# ALU.net
KiCad netlist of a schematic drawn in EAGLE
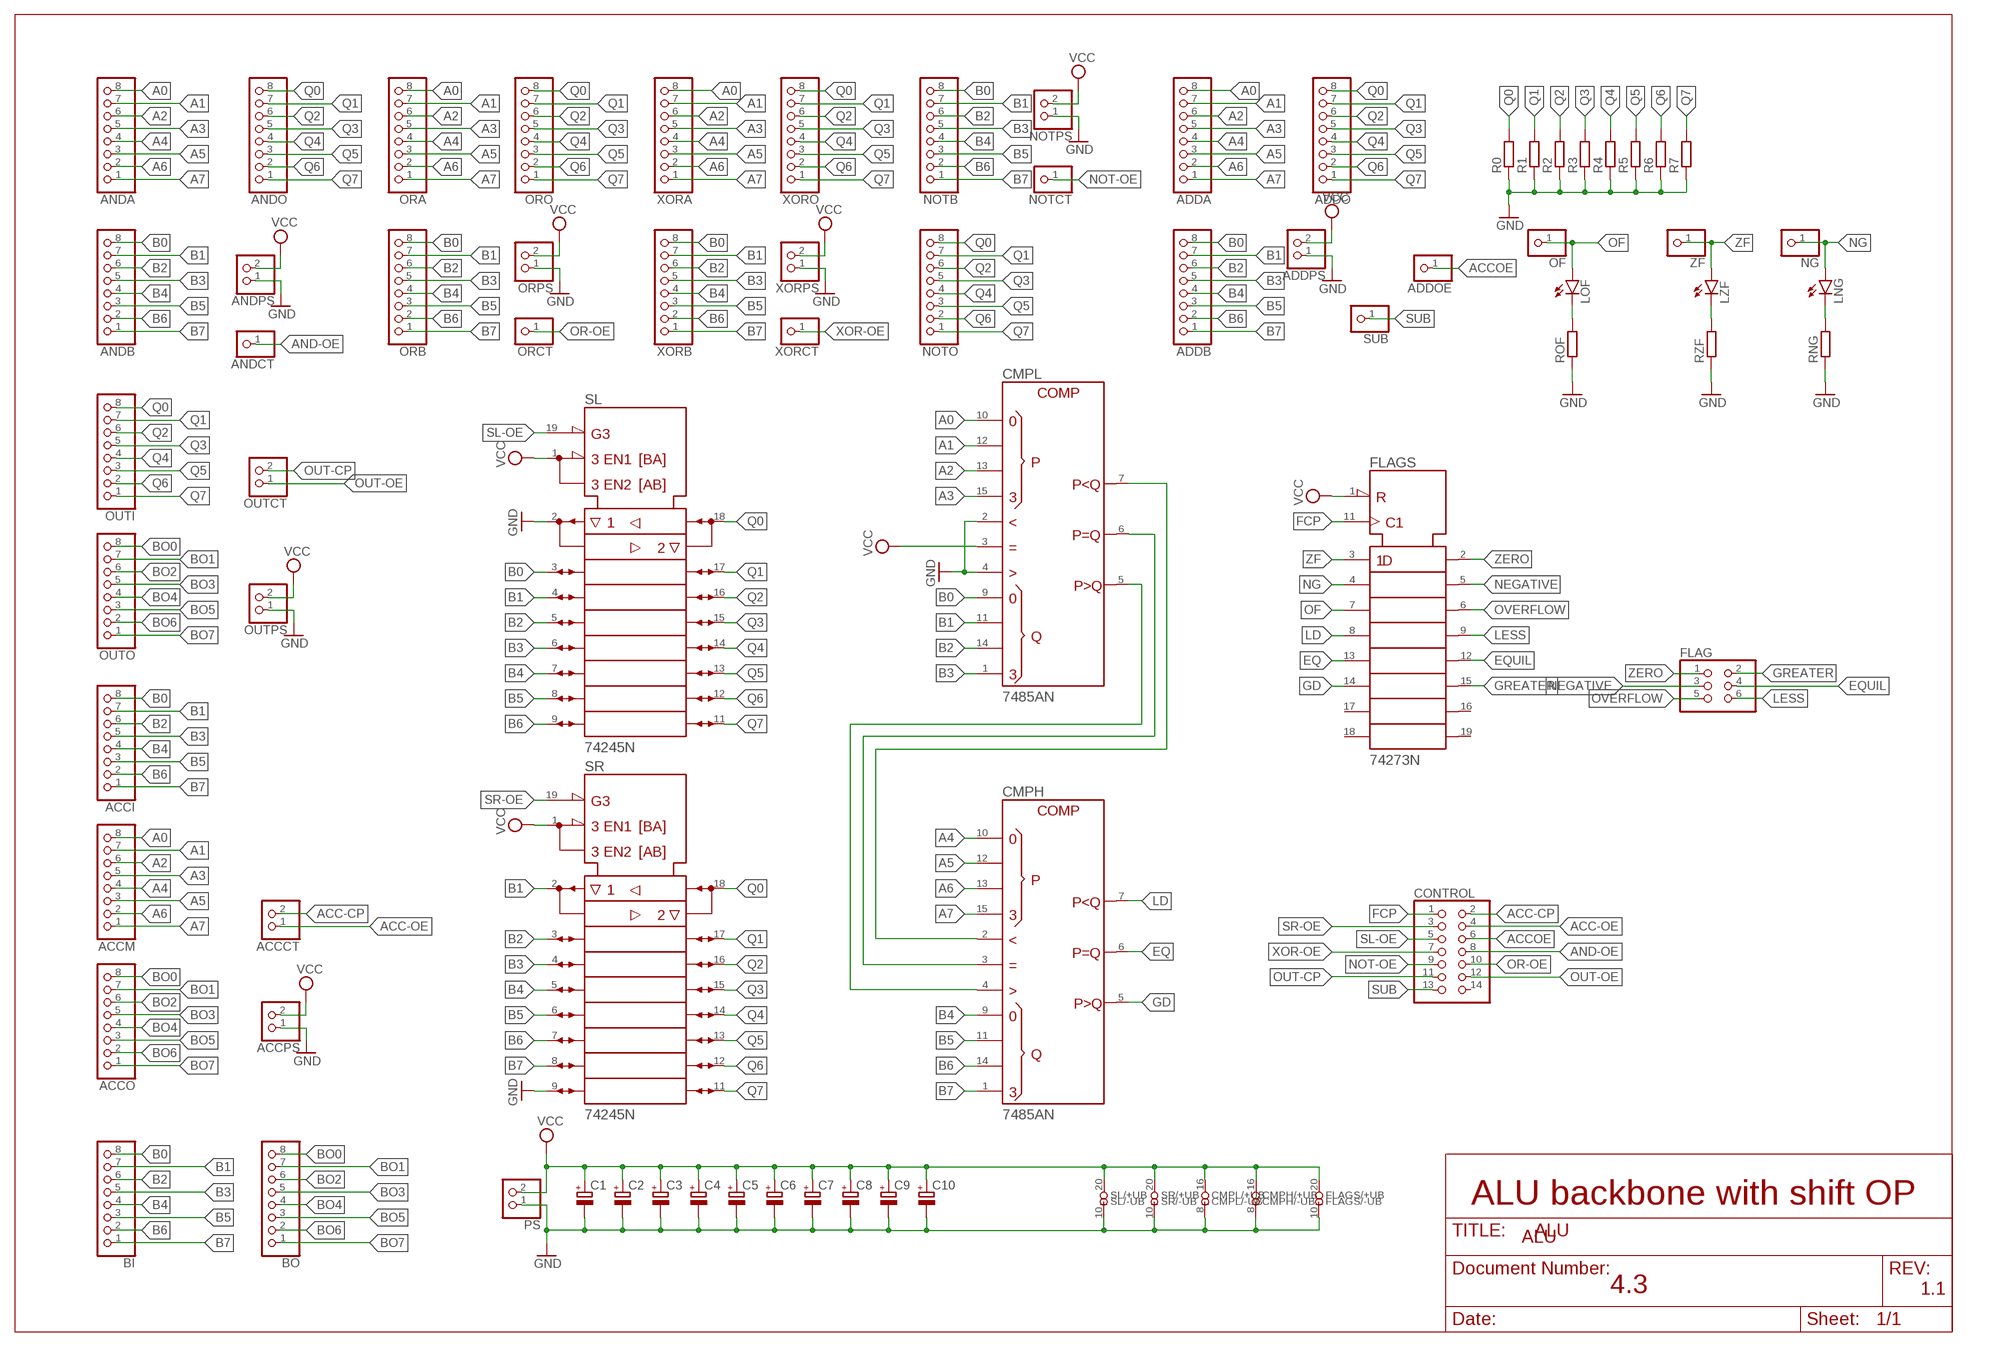
[diagram p0: schematic, sheet 1]

(export (version "E")
  (design (tool "Eeschema 10.0.6"))
  (components
    (comp (ref "ACCCT")
      (value "PINHD-1X2")
      (footprint "eagle-import:1X02")
      (libsource (lib "eagle-import") (part "PINHD-1X2"))
    )
    (comp (ref "ACCI")
      (value "PINHD-1X8")
      (footprint "eagle-import:1X08")
      (libsource (lib "eagle-import") (part "PINHD-1X8"))
    )
    (comp (ref "ACCM")
      (value "PINHD-1X8")
      (footprint "eagle-import:1X08")
      (libsource (lib "eagle-import") (part "PINHD-1X8"))
    )
    (comp (ref "ACCO")
      (value "PINHD-1X8")
      (footprint "eagle-import:1X08")
      (libsource (lib "eagle-import") (part "PINHD-1X8"))
    )
    (comp (ref "ACCPS")
      (value "PINHD-1X2")
      (footprint "eagle-import:1X02")
      (libsource (lib "eagle-import") (part "PINHD-1X2"))
    )
    (comp (ref "ADDA")
      (value "PINHD-1X8")
      (footprint "eagle-import:1X08")
      (libsource (lib "eagle-import") (part "PINHD-1X8"))
    )
    (comp (ref "ADDB")
      (value "PINHD-1X8")
      (footprint "eagle-import:1X08")
      (libsource (lib "eagle-import") (part "PINHD-1X8"))
    )
    (comp (ref "ADDO")
      (value "PINHD-1X8")
      (footprint "eagle-import:1X08")
      (libsource (lib "eagle-import") (part "PINHD-1X8"))
    )
    (comp (ref "ADDOE")
      (value "PINHD-1X1")
      (footprint "eagle-import:1X01")
      (libsource (lib "eagle-import") (part "PINHD-1X1"))
    )
    (comp (ref "ADDPS")
      (value "PINHD-1X2")
      (footprint "eagle-import:1X02")
      (libsource (lib "eagle-import") (part "PINHD-1X2"))
    )
    (comp (ref "ANDA")
      (value "PINHD-1X8")
      (footprint "eagle-import:1X08")
      (libsource (lib "eagle-import") (part "PINHD-1X8"))
    )
    (comp (ref "ANDB")
      (value "PINHD-1X8")
      (footprint "eagle-import:1X08")
      (libsource (lib "eagle-import") (part "PINHD-1X8"))
    )
    (comp (ref "ANDCT")
      (value "PINHD-1X1")
      (footprint "eagle-import:1X01")
      (libsource (lib "eagle-import") (part "PINHD-1X1"))
    )
    (comp (ref "ANDO")
      (value "PINHD-1X8")
      (footprint "eagle-import:1X08")
      (libsource (lib "eagle-import") (part "PINHD-1X8"))
    )
    (comp (ref "ANDPS")
      (value "PINHD-1X2")
      (footprint "eagle-import:1X02")
      (libsource (lib "eagle-import") (part "PINHD-1X2"))
    )
    (comp (ref "BI")
      (value "PINHD-1X8")
      (footprint "eagle-import:1X08")
      (libsource (lib "eagle-import") (part "PINHD-1X8"))
    )
    (comp (ref "BO")
      (value "PINHD-1X8")
      (footprint "eagle-import:1X08")
      (libsource (lib "eagle-import") (part "PINHD-1X8"))
    )
    (comp (ref "C1")
      (value "CPOL-EUE2.5-6")
      (footprint "eagle-import:E2,5-6")
      (libsource (lib "eagle-import") (part "CPOL-EUE2.5-6"))
    )
    (comp (ref "C2")
      (value "CPOL-EUE2.5-6")
      (footprint "eagle-import:E2,5-6")
      (libsource (lib "eagle-import") (part "CPOL-EUE2.5-6"))
    )
    (comp (ref "C3")
      (value "CPOL-EUE2.5-6")
      (footprint "eagle-import:E2,5-6")
      (libsource (lib "eagle-import") (part "CPOL-EUE2.5-6"))
    )
    (comp (ref "C4")
      (value "CPOL-EUE2.5-6")
      (footprint "eagle-import:E2,5-6")
      (libsource (lib "eagle-import") (part "CPOL-EUE2.5-6"))
    )
    (comp (ref "C5")
      (value "CPOL-EUE2.5-6")
      (footprint "eagle-import:E2,5-6")
      (libsource (lib "eagle-import") (part "CPOL-EUE2.5-6"))
    )
    (comp (ref "C6")
      (value "CPOL-EUE2.5-6")
      (footprint "eagle-import:E2,5-6")
      (libsource (lib "eagle-import") (part "CPOL-EUE2.5-6"))
    )
    (comp (ref "C7")
      (value "CPOL-EUE2.5-6")
      (footprint "eagle-import:E2,5-6")
      (libsource (lib "eagle-import") (part "CPOL-EUE2.5-6"))
    )
    (comp (ref "C8")
      (value "CPOL-EUE2.5-6")
      (footprint "eagle-import:E2,5-6")
      (libsource (lib "eagle-import") (part "CPOL-EUE2.5-6"))
    )
    (comp (ref "C9")
      (value "CPOL-EUE2.5-6")
      (footprint "eagle-import:E2,5-6")
      (libsource (lib "eagle-import") (part "CPOL-EUE2.5-6"))
    )
    (comp (ref "C10")
      (value "CPOL-EUE2.5-6")
      (footprint "eagle-import:E2,5-6")
      (libsource (lib "eagle-import") (part "CPOL-EUE2.5-6"))
    )
    (comp (ref "CMPH")
      (value "7485AN")
      (footprint "eagle-import:DIL16")
      (libsource (lib "eagle-import") (part "7485AN"))
    )
    (comp (ref "CMPL")
      (value "7485AN")
      (footprint "eagle-import:DIL16")
      (libsource (lib "eagle-import") (part "7485AN"))
    )
    (comp (ref "CONTROL")
      (value "PINHD-2X7")
      (footprint "eagle-import:2X07")
      (libsource (lib "eagle-import") (part "PINHD-2X7"))
    )
    (comp (ref "FLAG")
      (value "PINHD-2X3")
      (footprint "eagle-import:2X03")
      (libsource (lib "eagle-import") (part "PINHD-2X3"))
    )
    (comp (ref "FLAGS")
      (value "74273N")
      (footprint "eagle-import:DIL20")
      (libsource (lib "eagle-import") (part "74273N"))
    )
    (comp (ref "LNG")
      (value "LED5MM")
      (footprint "eagle-import:LED5MM")
      (libsource (lib "eagle-import") (part "LED5MM"))
    )
    (comp (ref "LOF")
      (value "LED5MM")
      (footprint "eagle-import:LED5MM")
      (libsource (lib "eagle-import") (part "LED5MM"))
    )
    (comp (ref "LZF")
      (value "LED5MM")
      (footprint "eagle-import:LED5MM")
      (libsource (lib "eagle-import") (part "LED5MM"))
    )
    (comp (ref "NG")
      (value "PINHD-1X1")
      (footprint "eagle-import:1X01")
      (libsource (lib "eagle-import") (part "PINHD-1X1"))
    )
    (comp (ref "NOTB")
      (value "PINHD-1X8")
      (footprint "eagle-import:1X08")
      (libsource (lib "eagle-import") (part "PINHD-1X8"))
    )
    (comp (ref "NOTCT")
      (value "PINHD-1X1")
      (footprint "eagle-import:1X01")
      (libsource (lib "eagle-import") (part "PINHD-1X1"))
    )
    (comp (ref "NOTO")
      (value "PINHD-1X8")
      (footprint "eagle-import:1X08")
      (libsource (lib "eagle-import") (part "PINHD-1X8"))
    )
    (comp (ref "NOTPS")
      (value "PINHD-1X2")
      (footprint "eagle-import:1X02")
      (libsource (lib "eagle-import") (part "PINHD-1X2"))
    )
    (comp (ref "OF")
      (value "PINHD-1X1")
      (footprint "eagle-import:1X01")
      (libsource (lib "eagle-import") (part "PINHD-1X1"))
    )
    (comp (ref "ORA")
      (value "PINHD-1X8")
      (footprint "eagle-import:1X08")
      (libsource (lib "eagle-import") (part "PINHD-1X8"))
    )
    (comp (ref "ORB")
      (value "PINHD-1X8")
      (footprint "eagle-import:1X08")
      (libsource (lib "eagle-import") (part "PINHD-1X8"))
    )
    (comp (ref "ORCT")
      (value "PINHD-1X1")
      (footprint "eagle-import:1X01")
      (libsource (lib "eagle-import") (part "PINHD-1X1"))
    )
    (comp (ref "ORO")
      (value "PINHD-1X8")
      (footprint "eagle-import:1X08")
      (libsource (lib "eagle-import") (part "PINHD-1X8"))
    )
    (comp (ref "ORPS")
      (value "PINHD-1X2")
      (footprint "eagle-import:1X02")
      (libsource (lib "eagle-import") (part "PINHD-1X2"))
    )
    (comp (ref "OUTCT")
      (value "PINHD-1X2")
      (footprint "eagle-import:1X02")
      (libsource (lib "eagle-import") (part "PINHD-1X2"))
    )
    (comp (ref "OUTI")
      (value "PINHD-1X8")
      (footprint "eagle-import:1X08")
      (libsource (lib "eagle-import") (part "PINHD-1X8"))
    )
    (comp (ref "OUTO")
      (value "PINHD-1X8")
      (footprint "eagle-import:1X08")
      (libsource (lib "eagle-import") (part "PINHD-1X8"))
    )
    (comp (ref "OUTPS")
      (value "PINHD-1X2")
      (footprint "eagle-import:1X02")
      (libsource (lib "eagle-import") (part "PINHD-1X2"))
    )
    (comp (ref "PS")
      (value "PINHD-1X2")
      (footprint "eagle-import:1X02")
      (libsource (lib "eagle-import") (part "PINHD-1X2"))
    )
    (comp (ref "R0")
      (value "R-EU_0204/7")
      (footprint "eagle-import:0204_7")
      (libsource (lib "eagle-import") (part "R-EU_0204/7"))
    )
    (comp (ref "R1")
      (value "R-EU_0204/7")
      (footprint "eagle-import:0204_7")
      (libsource (lib "eagle-import") (part "R-EU_0204/7"))
    )
    (comp (ref "R2")
      (value "R-EU_0204/7")
      (footprint "eagle-import:0204_7")
      (libsource (lib "eagle-import") (part "R-EU_0204/7"))
    )
    (comp (ref "R3")
      (value "R-EU_0204/7")
      (footprint "eagle-import:0204_7")
      (libsource (lib "eagle-import") (part "R-EU_0204/7"))
    )
    (comp (ref "R4")
      (value "R-EU_0204/7")
      (footprint "eagle-import:0204_7")
      (libsource (lib "eagle-import") (part "R-EU_0204/7"))
    )
    (comp (ref "R5")
      (value "R-EU_0204/7")
      (footprint "eagle-import:0204_7")
      (libsource (lib "eagle-import") (part "R-EU_0204/7"))
    )
    (comp (ref "R6")
      (value "R-EU_0204/7")
      (footprint "eagle-import:0204_7")
      (libsource (lib "eagle-import") (part "R-EU_0204/7"))
    )
    (comp (ref "R7")
      (value "R-EU_0204/7")
      (footprint "eagle-import:0204_7")
      (libsource (lib "eagle-import") (part "R-EU_0204/7"))
    )
    (comp (ref "RNG")
      (value "R-EU_0204/7")
      (footprint "eagle-import:0204_7")
      (libsource (lib "eagle-import") (part "R-EU_0204/7"))
    )
    (comp (ref "ROF")
      (value "R-EU_0204/7")
      (footprint "eagle-import:0204_7")
      (libsource (lib "eagle-import") (part "R-EU_0204/7"))
    )
    (comp (ref "RZF")
      (value "R-EU_0204/7")
      (footprint "eagle-import:0204_7")
      (libsource (lib "eagle-import") (part "R-EU_0204/7"))
    )
    (comp (ref "SL")
      (value "74245N")
      (footprint "eagle-import:DIL20")
      (libsource (lib "eagle-import") (part "74245N"))
    )
    (comp (ref "SR")
      (value "74245N")
      (footprint "eagle-import:DIL20")
      (libsource (lib "eagle-import") (part "74245N"))
    )
    (comp (ref "SUB")
      (value "PINHD-1X1")
      (footprint "eagle-import:1X01")
      (libsource (lib "eagle-import") (part "PINHD-1X1"))
    )
    (comp (ref "XORA")
      (value "PINHD-1X8")
      (footprint "eagle-import:1X08")
      (libsource (lib "eagle-import") (part "PINHD-1X8"))
    )
    (comp (ref "XORB")
      (value "PINHD-1X8")
      (footprint "eagle-import:1X08")
      (libsource (lib "eagle-import") (part "PINHD-1X8"))
    )
    (comp (ref "XORCT")
      (value "PINHD-1X1")
      (footprint "eagle-import:1X01")
      (libsource (lib "eagle-import") (part "PINHD-1X1"))
    )
    (comp (ref "XORO")
      (value "PINHD-1X8")
      (footprint "eagle-import:1X08")
      (libsource (lib "eagle-import") (part "PINHD-1X8"))
    )
    (comp (ref "XORPS")
      (value "PINHD-1X2")
      (footprint "eagle-import:1X02")
      (libsource (lib "eagle-import") (part "PINHD-1X2"))
    )
    (comp (ref "ZF")
      (value "PINHD-1X1")
      (footprint "eagle-import:1X01")
      (libsource (lib "eagle-import") (part "PINHD-1X1"))
    )
  )
  (nets
    (net (code "1") (name "A0") (class "Default")
      (node (ref "ACCM") (pin "8") (pinfunction "8_8") (pintype "passive"))
      (node (ref "ADDA") (pin "8") (pinfunction "8_8") (pintype "passive"))
      (node (ref "ANDA") (pin "8") (pinfunction "8_8") (pintype "passive"))
      (node (ref "CMPL") (pin "10") (pinfunction "P0_10") (pintype "input"))
      (node (ref "ORA") (pin "8") (pinfunction "8_8") (pintype "passive"))
      (node (ref "XORA") (pin "8") (pinfunction "8_8") (pintype "passive"))
    )
    (net (code "2") (name "A1") (class "Default")
      (node (ref "ACCM") (pin "7") (pinfunction "7_7") (pintype "passive"))
      (node (ref "ADDA") (pin "7") (pinfunction "7_7") (pintype "passive"))
      (node (ref "ANDA") (pin "7") (pinfunction "7_7") (pintype "passive"))
      (node (ref "CMPL") (pin "12") (pinfunction "P1_12") (pintype "input"))
      (node (ref "ORA") (pin "7") (pinfunction "7_7") (pintype "passive"))
      (node (ref "XORA") (pin "7") (pinfunction "7_7") (pintype "passive"))
    )
    (net (code "3") (name "A2") (class "Default")
      (node (ref "ACCM") (pin "6") (pinfunction "6_6") (pintype "passive"))
      (node (ref "ADDA") (pin "6") (pinfunction "6_6") (pintype "passive"))
      (node (ref "ANDA") (pin "6") (pinfunction "6_6") (pintype "passive"))
      (node (ref "CMPL") (pin "13") (pinfunction "P2_13") (pintype "input"))
      (node (ref "ORA") (pin "6") (pinfunction "6_6") (pintype "passive"))
      (node (ref "XORA") (pin "6") (pinfunction "6_6") (pintype "passive"))
    )
    (net (code "4") (name "A3") (class "Default")
      (node (ref "ACCM") (pin "5") (pinfunction "5_5") (pintype "passive"))
      (node (ref "ADDA") (pin "5") (pinfunction "5_5") (pintype "passive"))
      (node (ref "ANDA") (pin "5") (pinfunction "5_5") (pintype "passive"))
      (node (ref "CMPL") (pin "15") (pinfunction "P3_15") (pintype "input"))
      (node (ref "ORA") (pin "5") (pinfunction "5_5") (pintype "passive"))
      (node (ref "XORA") (pin "5") (pinfunction "5_5") (pintype "passive"))
    )
    (net (code "5") (name "A4") (class "Default")
      (node (ref "ACCM") (pin "4") (pinfunction "4_4") (pintype "passive"))
      (node (ref "ADDA") (pin "4") (pinfunction "4_4") (pintype "passive"))
      (node (ref "ANDA") (pin "4") (pinfunction "4_4") (pintype "passive"))
      (node (ref "CMPH") (pin "10") (pinfunction "P0_10") (pintype "input"))
      (node (ref "ORA") (pin "4") (pinfunction "4_4") (pintype "passive"))
      (node (ref "XORA") (pin "4") (pinfunction "4_4") (pintype "passive"))
    )
    (net (code "6") (name "A5") (class "Default")
      (node (ref "ACCM") (pin "3") (pinfunction "3_3") (pintype "passive"))
      (node (ref "ADDA") (pin "3") (pinfunction "3_3") (pintype "passive"))
      (node (ref "ANDA") (pin "3") (pinfunction "3_3") (pintype "passive"))
      (node (ref "CMPH") (pin "12") (pinfunction "P1_12") (pintype "input"))
      (node (ref "ORA") (pin "3") (pinfunction "3_3") (pintype "passive"))
      (node (ref "XORA") (pin "3") (pinfunction "3_3") (pintype "passive"))
    )
    (net (code "7") (name "A6") (class "Default")
      (node (ref "ACCM") (pin "2") (pinfunction "2_2") (pintype "passive"))
      (node (ref "ADDA") (pin "2") (pinfunction "2_2") (pintype "passive"))
      (node (ref "ANDA") (pin "2") (pinfunction "2_2") (pintype "passive"))
      (node (ref "CMPH") (pin "13") (pinfunction "P2_13") (pintype "input"))
      (node (ref "ORA") (pin "2") (pinfunction "2_2") (pintype "passive"))
      (node (ref "XORA") (pin "2") (pinfunction "2_2") (pintype "passive"))
    )
    (net (code "8") (name "A7") (class "Default")
      (node (ref "ACCM") (pin "1") (pinfunction "1_1") (pintype "passive"))
      (node (ref "ADDA") (pin "1") (pinfunction "1_1") (pintype "passive"))
      (node (ref "ANDA") (pin "1") (pinfunction "1_1") (pintype "passive"))
      (node (ref "CMPH") (pin "15") (pinfunction "P3_15") (pintype "input"))
      (node (ref "ORA") (pin "1") (pinfunction "1_1") (pintype "passive"))
      (node (ref "XORA") (pin "1") (pinfunction "1_1") (pintype "passive"))
    )
    (net (code "9") (name "ACC-CP") (class "Default")
      (node (ref "ACCCT") (pin "2") (pinfunction "2_2") (pintype "passive"))
      (node (ref "CONTROL") (pin "2") (pinfunction "2_2") (pintype "passive"))
    )
    (net (code "10") (name "ACC-OE") (class "Default")
      (node (ref "ACCCT") (pin "1") (pinfunction "1_1") (pintype "passive"))
      (node (ref "CONTROL") (pin "4") (pinfunction "4_4") (pintype "passive"))
    )
    (net (code "11") (name "ACCOE") (class "Default")
      (node (ref "ADDOE") (pin "1") (pinfunction "1_1") (pintype "passive"))
      (node (ref "CONTROL") (pin "6") (pinfunction "6_6") (pintype "passive"))
    )
    (net (code "12") (name "AND-OE") (class "Default")
      (node (ref "ANDCT") (pin "1") (pinfunction "1_1") (pintype "passive"))
      (node (ref "CONTROL") (pin "8") (pinfunction "8_8") (pintype "passive"))
    )
    (net (code "13") (name "B0") (class "Default")
      (node (ref "ACCI") (pin "8") (pinfunction "8_8") (pintype "passive"))
      (node (ref "ADDB") (pin "8") (pinfunction "8_8") (pintype "passive"))
      (node (ref "ANDB") (pin "8") (pinfunction "8_8") (pintype "passive"))
      (node (ref "BI") (pin "8") (pinfunction "8_8") (pintype "passive"))
      (node (ref "CMPL") (pin "9") (pinfunction "Q0_9") (pintype "input"))
      (node (ref "NOTB") (pin "8") (pinfunction "8_8") (pintype "passive"))
      (node (ref "ORB") (pin "8") (pinfunction "8_8") (pintype "passive"))
      (node (ref "SL") (pin "3") (pinfunction "A2_3") (pintype "bidirectional"))
      (node (ref "XORB") (pin "8") (pinfunction "8_8") (pintype "passive"))
    )
    (net (code "14") (name "B1") (class "Default")
      (node (ref "ACCI") (pin "7") (pinfunction "7_7") (pintype "passive"))
      (node (ref "ADDB") (pin "7") (pinfunction "7_7") (pintype "passive"))
      (node (ref "ANDB") (pin "7") (pinfunction "7_7") (pintype "passive"))
      (node (ref "BI") (pin "7") (pinfunction "7_7") (pintype "passive"))
      (node (ref "CMPL") (pin "11") (pinfunction "Q1_11") (pintype "input"))
      (node (ref "NOTB") (pin "7") (pinfunction "7_7") (pintype "passive"))
      (node (ref "ORB") (pin "7") (pinfunction "7_7") (pintype "passive"))
      (node (ref "SL") (pin "4") (pinfunction "A3_4") (pintype "bidirectional"))
      (node (ref "SR") (pin "2") (pinfunction "A1_2") (pintype "bidirectional"))
      (node (ref "XORB") (pin "7") (pinfunction "7_7") (pintype "passive"))
    )
    (net (code "15") (name "B2") (class "Default")
      (node (ref "ACCI") (pin "6") (pinfunction "6_6") (pintype "passive"))
      (node (ref "ADDB") (pin "6") (pinfunction "6_6") (pintype "passive"))
      (node (ref "ANDB") (pin "6") (pinfunction "6_6") (pintype "passive"))
      (node (ref "BI") (pin "6") (pinfunction "6_6") (pintype "passive"))
      (node (ref "CMPL") (pin "14") (pinfunction "Q2_14") (pintype "input"))
      (node (ref "NOTB") (pin "6") (pinfunction "6_6") (pintype "passive"))
      (node (ref "ORB") (pin "6") (pinfunction "6_6") (pintype "passive"))
      (node (ref "SL") (pin "5") (pinfunction "A4_5") (pintype "bidirectional"))
      (node (ref "SR") (pin "3") (pinfunction "A2_3") (pintype "bidirectional"))
      (node (ref "XORB") (pin "6") (pinfunction "6_6") (pintype "passive"))
    )
    (net (code "16") (name "B3") (class "Default")
      (node (ref "ACCI") (pin "5") (pinfunction "5_5") (pintype "passive"))
      (node (ref "ADDB") (pin "5") (pinfunction "5_5") (pintype "passive"))
      (node (ref "ANDB") (pin "5") (pinfunction "5_5") (pintype "passive"))
      (node (ref "BI") (pin "5") (pinfunction "5_5") (pintype "passive"))
      (node (ref "CMPL") (pin "1") (pinfunction "Q3_1") (pintype "input"))
      (node (ref "NOTB") (pin "5") (pinfunction "5_5") (pintype "passive"))
      (node (ref "ORB") (pin "5") (pinfunction "5_5") (pintype "passive"))
      (node (ref "SL") (pin "6") (pinfunction "A5_6") (pintype "bidirectional"))
      (node (ref "SR") (pin "4") (pinfunction "A3_4") (pintype "bidirectional"))
      (node (ref "XORB") (pin "5") (pinfunction "5_5") (pintype "passive"))
    )
    (net (code "17") (name "B4") (class "Default")
      (node (ref "ACCI") (pin "4") (pinfunction "4_4") (pintype "passive"))
      (node (ref "ADDB") (pin "4") (pinfunction "4_4") (pintype "passive"))
      (node (ref "ANDB") (pin "4") (pinfunction "4_4") (pintype "passive"))
      (node (ref "BI") (pin "4") (pinfunction "4_4") (pintype "passive"))
      (node (ref "CMPH") (pin "9") (pinfunction "Q0_9") (pintype "input"))
      (node (ref "NOTB") (pin "4") (pinfunction "4_4") (pintype "passive"))
      (node (ref "ORB") (pin "4") (pinfunction "4_4") (pintype "passive"))
      (node (ref "SL") (pin "7") (pinfunction "A6_7") (pintype "bidirectional"))
      (node (ref "SR") (pin "5") (pinfunction "A4_5") (pintype "bidirectional"))
      (node (ref "XORB") (pin "4") (pinfunction "4_4") (pintype "passive"))
    )
    (net (code "18") (name "B5") (class "Default")
      (node (ref "ACCI") (pin "3") (pinfunction "3_3") (pintype "passive"))
      (node (ref "ADDB") (pin "3") (pinfunction "3_3") (pintype "passive"))
      (node (ref "ANDB") (pin "3") (pinfunction "3_3") (pintype "passive"))
      (node (ref "BI") (pin "3") (pinfunction "3_3") (pintype "passive"))
      (node (ref "CMPH") (pin "11") (pinfunction "Q1_11") (pintype "input"))
      (node (ref "NOTB") (pin "3") (pinfunction "3_3") (pintype "passive"))
      (node (ref "ORB") (pin "3") (pinfunction "3_3") (pintype "passive"))
      (node (ref "SL") (pin "8") (pinfunction "A7_8") (pintype "bidirectional"))
      (node (ref "SR") (pin "6") (pinfunction "A5_6") (pintype "bidirectional"))
      (node (ref "XORB") (pin "3") (pinfunction "3_3") (pintype "passive"))
    )
    (net (code "19") (name "B6") (class "Default")
      (node (ref "ACCI") (pin "2") (pinfunction "2_2") (pintype "passive"))
      (node (ref "ADDB") (pin "2") (pinfunction "2_2") (pintype "passive"))
      (node (ref "ANDB") (pin "2") (pinfunction "2_2") (pintype "passive"))
      (node (ref "BI") (pin "2") (pinfunction "2_2") (pintype "passive"))
      (node (ref "CMPH") (pin "14") (pinfunction "Q2_14") (pintype "input"))
      (node (ref "NOTB") (pin "2") (pinfunction "2_2") (pintype "passive"))
      (node (ref "ORB") (pin "2") (pinfunction "2_2") (pintype "passive"))
      (node (ref "SL") (pin "9") (pinfunction "A8_9") (pintype "bidirectional"))
      (node (ref "SR") (pin "7") (pinfunction "A6_7") (pintype "bidirectional"))
      (node (ref "XORB") (pin "2") (pinfunction "2_2") (pintype "passive"))
    )
    (net (code "20") (name "B7") (class "Default")
      (node (ref "ACCI") (pin "1") (pinfunction "1_1") (pintype "passive"))
      (node (ref "ADDB") (pin "1") (pinfunction "1_1") (pintype "passive"))
      (node (ref "ANDB") (pin "1") (pinfunction "1_1") (pintype "passive"))
      (node (ref "BI") (pin "1") (pinfunction "1_1") (pintype "passive"))
      (node (ref "CMPH") (pin "1") (pinfunction "Q3_1") (pintype "input"))
      (node (ref "NOTB") (pin "1") (pinfunction "1_1") (pintype "passive"))
      (node (ref "ORB") (pin "1") (pinfunction "1_1") (pintype "passive"))
      (node (ref "SR") (pin "8") (pinfunction "A7_8") (pintype "bidirectional"))
      (node (ref "XORB") (pin "1") (pinfunction "1_1") (pintype "passive"))
    )
    (net (code "21") (name "BO0") (class "Default")
      (node (ref "ACCO") (pin "8") (pinfunction "8_8") (pintype "passive"))
      (node (ref "BO") (pin "8") (pinfunction "8_8") (pintype "passive"))
      (node (ref "OUTO") (pin "8") (pinfunction "8_8") (pintype "passive"))
    )
    (net (code "22") (name "BO1") (class "Default")
      (node (ref "ACCO") (pin "7") (pinfunction "7_7") (pintype "passive"))
      (node (ref "BO") (pin "7") (pinfunction "7_7") (pintype "passive"))
      (node (ref "OUTO") (pin "7") (pinfunction "7_7") (pintype "passive"))
    )
    (net (code "23") (name "BO2") (class "Default")
      (node (ref "ACCO") (pin "6") (pinfunction "6_6") (pintype "passive"))
      (node (ref "BO") (pin "6") (pinfunction "6_6") (pintype "passive"))
      (node (ref "OUTO") (pin "6") (pinfunction "6_6") (pintype "passive"))
    )
    (net (code "24") (name "BO3") (class "Default")
      (node (ref "ACCO") (pin "5") (pinfunction "5_5") (pintype "passive"))
      (node (ref "BO") (pin "5") (pinfunction "5_5") (pintype "passive"))
      (node (ref "OUTO") (pin "5") (pinfunction "5_5") (pintype "passive"))
    )
    (net (code "25") (name "BO4") (class "Default")
      (node (ref "ACCO") (pin "4") (pinfunction "4_4") (pintype "passive"))
      (node (ref "BO") (pin "4") (pinfunction "4_4") (pintype "passive"))
      (node (ref "OUTO") (pin "4") (pinfunction "4_4") (pintype "passive"))
    )
    (net (code "26") (name "BO5") (class "Default")
      (node (ref "ACCO") (pin "3") (pinfunction "3_3") (pintype "passive"))
      (node (ref "BO") (pin "3") (pinfunction "3_3") (pintype "passive"))
      (node (ref "OUTO") (pin "3") (pinfunction "3_3") (pintype "passive"))
    )
    (net (code "27") (name "BO6") (class "Default")
      (node (ref "ACCO") (pin "2") (pinfunction "2_2") (pintype "passive"))
      (node (ref "BO") (pin "2") (pinfunction "2_2") (pintype "passive"))
      (node (ref "OUTO") (pin "2") (pinfunction "2_2") (pintype "passive"))
    )
    (net (code "28") (name "BO7") (class "Default")
      (node (ref "ACCO") (pin "1") (pinfunction "1_1") (pintype "passive"))
      (node (ref "BO") (pin "1") (pinfunction "1_1") (pintype "passive"))
      (node (ref "OUTO") (pin "1") (pinfunction "1_1") (pintype "passive"))
    )
    (net (code "29") (name "EQ") (class "Default")
      (node (ref "CMPH") (pin "6") (pinfunction "PEQQ_6") (pintype "output"))
      (node (ref "FLAGS") (pin "13") (pinfunction "5D_13") (pintype "input"))
    )
    (net (code "30") (name "EQUIL") (class "Default")
      (node (ref "FLAG") (pin "4") (pinfunction "4_4") (pintype "passive"))
      (node (ref "FLAGS") (pin "12") (pinfunction "5Q_12") (pintype "output"))
    )
    (net (code "31") (name "FCP") (class "Default")
      (node (ref "CONTROL") (pin "1") (pinfunction "1_1") (pintype "passive"))
      (node (ref "FLAGS") (pin "11") (pinfunction "CLK_11") (pintype "input"))
    )
    (net (code "32") (name "GD") (class "Default")
      (node (ref "CMPH") (pin "5") (pinfunction "PGTQ_5") (pintype "output"))
      (node (ref "FLAGS") (pin "14") (pinfunction "6D_14") (pintype "input"))
    )
    (net (code "33") (name "GND") (class "Default")
      (node (ref "ACCPS") (pin "1") (pinfunction "1_1") (pintype "passive"))
      (node (ref "ADDPS") (pin "1") (pinfunction "1_1") (pintype "passive"))
      (node (ref "ANDPS") (pin "1") (pinfunction "1_1") (pintype "passive"))
      (node (ref "C1") (pin "-") (pinfunction "-_-") (pintype "passive"))
      (node (ref "C10") (pin "-") (pinfunction "-_-") (pintype "passive"))
      (node (ref "C2") (pin "-") (pinfunction "-_-") (pintype "passive"))
      (node (ref "C3") (pin "-") (pinfunction "-_-") (pintype "passive"))
      (node (ref "C4") (pin "-") (pinfunction "-_-") (pintype "passive"))
      (node (ref "C5") (pin "-") (pinfunction "-_-") (pintype "passive"))
      (node (ref "C6") (pin "-") (pinfunction "-_-") (pintype "passive"))
      (node (ref "C7") (pin "-") (pinfunction "-_-") (pintype "passive"))
      (node (ref "C8") (pin "-") (pinfunction "-_-") (pintype "passive"))
      (node (ref "C9") (pin "-") (pinfunction "-_-") (pintype "passive"))
      (node (ref "CMPH") (pin "8") (pinfunction "-UB_8") (pintype "power_in"))
      (node (ref "CMPL") (pin "2") (pinfunction "PLTQ__2") (pintype "input"))
      (node (ref "CMPL") (pin "4") (pinfunction "PGTQ__4") (pintype "input"))
      (node (ref "CMPL") (pin "8") (pinfunction "-UB_8") (pintype "power_in"))
      (node (ref "FLAGS") (pin "10") (pinfunction "-UB_10") (pintype "power_in"))
      (node (ref "NOTPS") (pin "1") (pinfunction "1_1") (pintype "passive"))
      (node (ref "ORPS") (pin "1") (pinfunction "1_1") (pintype "passive"))
      (node (ref "OUTPS") (pin "1") (pinfunction "1_1") (pintype "passive"))
      (node (ref "PS") (pin "1") (pinfunction "1_1") (pintype "passive"))
      (node (ref "R0") (pin "1") (pinfunction "1_1") (pintype "passive"))
      (node (ref "R1") (pin "1") (pinfunction "1_1") (pintype "passive"))
      (node (ref "R2") (pin "1") (pinfunction "1_1") (pintype "passive"))
      (node (ref "R3") (pin "1") (pinfunction "1_1") (pintype "passive"))
      (node (ref "R4") (pin "1") (pinfunction "1_1") (pintype "passive"))
      (node (ref "R5") (pin "1") (pinfunction "1_1") (pintype "passive"))
      (node (ref "R6") (pin "1") (pinfunction "1_1") (pintype "passive"))
      (node (ref "R7") (pin "1") (pinfunction "1_1") (pintype "passive"))
      (node (ref "RNG") (pin "1") (pinfunction "1_1") (pintype "passive"))
      (node (ref "ROF") (pin "1") (pinfunction "1_1") (pintype "passive"))
      (node (ref "RZF") (pin "1") (pinfunction "1_1") (pintype "passive"))
      (node (ref "SL") (pin "10") (pinfunction "-UB_10") (pintype "power_in"))
      (node (ref "SL") (pin "2") (pinfunction "A1_2") (pintype "bidirectional"))
      (node (ref "SR") (pin "10") (pinfunction "-UB_10") (pintype "power_in"))
      (node (ref "SR") (pin "9") (pinfunction "A8_9") (pintype "bidirectional"))
      (node (ref "XORPS") (pin "1") (pinfunction "1_1") (pintype "passive"))
    )
    (net (code "34") (name "GREATER") (class "Default")
      (node (ref "FLAG") (pin "2") (pinfunction "2_2") (pintype "passive"))
      (node (ref "FLAGS") (pin "15") (pinfunction "6Q_15") (pintype "output"))
    )
    (net (code "35") (name "LD") (class "Default")
      (node (ref "CMPH") (pin "7") (pinfunction "PLTQ_7") (pintype "output"))
      (node (ref "FLAGS") (pin "8") (pinfunction "4D_8") (pintype "input"))
    )
    (net (code "36") (name "LESS") (class "Default")
      (node (ref "FLAG") (pin "6") (pinfunction "6_6") (pintype "passive"))
      (node (ref "FLAGS") (pin "9") (pinfunction "4Q_9") (pintype "output"))
    )
    (net (code "37") (name "NEGATIVE") (class "Default")
      (node (ref "FLAG") (pin "3") (pinfunction "3_3") (pintype "passive"))
      (node (ref "FLAGS") (pin "5") (pinfunction "2Q_5") (pintype "output"))
    )
    (net (code "38") (name "NG") (class "Default")
      (node (ref "FLAGS") (pin "4") (pinfunction "2D_4") (pintype "input"))
      (node (ref "LNG") (pin "A") (pinfunction "A_A") (pintype "passive"))
      (node (ref "NG") (pin "1") (pinfunction "1_1") (pintype "passive"))
    )
    (net (code "39") (name "NOT-OE") (class "Default")
      (node (ref "CONTROL") (pin "9") (pinfunction "9_9") (pintype "passive"))
      (node (ref "NOTCT") (pin "1") (pinfunction "1_1") (pintype "passive"))
    )
    (net (code "40") (name "Net-(CMPHC-PEQQ_)") (class "Default")
      (node (ref "CMPH") (pin "3") (pinfunction "PEQQ__3") (pintype "input"))
      (node (ref "CMPL") (pin "6") (pinfunction "PEQQ_6") (pintype "output"))
    )
    (net (code "41") (name "Net-(CMPHC-PGTQ_)") (class "Default")
      (node (ref "CMPH") (pin "4") (pinfunction "PGTQ__4") (pintype "input"))
      (node (ref "CMPL") (pin "5") (pinfunction "PGTQ_5") (pintype "output"))
    )
    (net (code "42") (name "Net-(CMPHC-PLTQ_)") (class "Default")
      (node (ref "CMPH") (pin "2") (pinfunction "PLTQ__2") (pintype "input"))
      (node (ref "CMPL") (pin "7") (pinfunction "PLTQ_7") (pintype "output"))
    )
    (net (code "43") (name "Net-(LNG-C)") (class "Default")
      (node (ref "LNG") (pin "K") (pinfunction "C_K") (pintype "passive"))
      (node (ref "RNG") (pin "2") (pinfunction "2_2") (pintype "passive"))
    )
    (net (code "44") (name "Net-(LOF-C)") (class "Default")
      (node (ref "LOF") (pin "K") (pinfunction "C_K") (pintype "passive"))
      (node (ref "ROF") (pin "2") (pinfunction "2_2") (pintype "passive"))
    )
    (net (code "45") (name "Net-(LZF-C)") (class "Default")
      (node (ref "LZF") (pin "K") (pinfunction "C_K") (pintype "passive"))
      (node (ref "RZF") (pin "2") (pinfunction "2_2") (pintype "passive"))
    )
    (net (code "46") (name "OF") (class "Default")
      (node (ref "FLAGS") (pin "7") (pinfunction "3D_7") (pintype "input"))
      (node (ref "LOF") (pin "A") (pinfunction "A_A") (pintype "passive"))
      (node (ref "OF") (pin "1") (pinfunction "1_1") (pintype "passive"))
    )
    (net (code "47") (name "OR-OE") (class "Default")
      (node (ref "CONTROL") (pin "10") (pinfunction "10_10") (pintype "passive"))
      (node (ref "ORCT") (pin "1") (pinfunction "1_1") (pintype "passive"))
    )
    (net (code "48") (name "OUT-CP") (class "Default")
      (node (ref "CONTROL") (pin "11") (pinfunction "11_11") (pintype "passive"))
      (node (ref "OUTCT") (pin "2") (pinfunction "2_2") (pintype "passive"))
    )
    (net (code "49") (name "OUT-OE") (class "Default")
      (node (ref "CONTROL") (pin "12") (pinfunction "12_12") (pintype "passive"))
      (node (ref "OUTCT") (pin "1") (pinfunction "1_1") (pintype "passive"))
    )
    (net (code "50") (name "OVERFLOW") (class "Default")
      (node (ref "FLAG") (pin "5") (pinfunction "5_5") (pintype "passive"))
      (node (ref "FLAGS") (pin "6") (pinfunction "3Q_6") (pintype "output"))
    )
    (net (code "51") (name "Q0") (class "Default")
      (node (ref "ADDO") (pin "8") (pinfunction "8_8") (pintype "passive"))
      (node (ref "ANDO") (pin "8") (pinfunction "8_8") (pintype "passive"))
      (node (ref "NOTO") (pin "8") (pinfunction "8_8") (pintype "passive"))
      (node (ref "ORO") (pin "8") (pinfunction "8_8") (pintype "passive"))
      (node (ref "OUTI") (pin "8") (pinfunction "8_8") (pintype "passive"))
      (node (ref "R0") (pin "2") (pinfunction "2_2") (pintype "passive"))
      (node (ref "SL") (pin "18") (pinfunction "B1_18") (pintype "bidirectional"))
      (node (ref "SR") (pin "18") (pinfunction "B1_18") (pintype "bidirectional"))
      (node (ref "XORO") (pin "8") (pinfunction "8_8") (pintype "passive"))
    )
    (net (code "52") (name "Q1") (class "Default")
      (node (ref "ADDO") (pin "7") (pinfunction "7_7") (pintype "passive"))
      (node (ref "ANDO") (pin "7") (pinfunction "7_7") (pintype "passive"))
      (node (ref "NOTO") (pin "7") (pinfunction "7_7") (pintype "passive"))
      (node (ref "ORO") (pin "7") (pinfunction "7_7") (pintype "passive"))
      (node (ref "OUTI") (pin "7") (pinfunction "7_7") (pintype "passive"))
      (node (ref "R1") (pin "2") (pinfunction "2_2") (pintype "passive"))
      (node (ref "SL") (pin "17") (pinfunction "B2_17") (pintype "bidirectional"))
      (node (ref "SR") (pin "17") (pinfunction "B2_17") (pintype "bidirectional"))
      (node (ref "XORO") (pin "7") (pinfunction "7_7") (pintype "passive"))
    )
    (net (code "53") (name "Q2") (class "Default")
      (node (ref "ADDO") (pin "6") (pinfunction "6_6") (pintype "passive"))
      (node (ref "ANDO") (pin "6") (pinfunction "6_6") (pintype "passive"))
      (node (ref "NOTO") (pin "6") (pinfunction "6_6") (pintype "passive"))
      (node (ref "ORO") (pin "6") (pinfunction "6_6") (pintype "passive"))
      (node (ref "OUTI") (pin "6") (pinfunction "6_6") (pintype "passive"))
      (node (ref "R2") (pin "2") (pinfunction "2_2") (pintype "passive"))
      (node (ref "SL") (pin "16") (pinfunction "B3_16") (pintype "bidirectional"))
      (node (ref "SR") (pin "16") (pinfunction "B3_16") (pintype "bidirectional"))
      (node (ref "XORO") (pin "6") (pinfunction "6_6") (pintype "passive"))
    )
    (net (code "54") (name "Q3") (class "Default")
      (node (ref "ADDO") (pin "5") (pinfunction "5_5") (pintype "passive"))
      (node (ref "ANDO") (pin "5") (pinfunction "5_5") (pintype "passive"))
      (node (ref "NOTO") (pin "5") (pinfunction "5_5") (pintype "passive"))
      (node (ref "ORO") (pin "5") (pinfunction "5_5") (pintype "passive"))
      (node (ref "OUTI") (pin "5") (pinfunction "5_5") (pintype "passive"))
      (node (ref "R3") (pin "2") (pinfunction "2_2") (pintype "passive"))
      (node (ref "SL") (pin "15") (pinfunction "B4_15") (pintype "bidirectional"))
      (node (ref "SR") (pin "15") (pinfunction "B4_15") (pintype "bidirectional"))
      (node (ref "XORO") (pin "5") (pinfunction "5_5") (pintype "passive"))
    )
    (net (code "55") (name "Q4") (class "Default")
      (node (ref "ADDO") (pin "4") (pinfunction "4_4") (pintype "passive"))
      (node (ref "ANDO") (pin "4") (pinfunction "4_4") (pintype "passive"))
      (node (ref "NOTO") (pin "4") (pinfunction "4_4") (pintype "passive"))
      (node (ref "ORO") (pin "4") (pinfunction "4_4") (pintype "passive"))
      (node (ref "OUTI") (pin "4") (pinfunction "4_4") (pintype "passive"))
      (node (ref "R4") (pin "2") (pinfunction "2_2") (pintype "passive"))
      (node (ref "SL") (pin "14") (pinfunction "B5_14") (pintype "bidirectional"))
      (node (ref "SR") (pin "14") (pinfunction "B5_14") (pintype "bidirectional"))
      (node (ref "XORO") (pin "4") (pinfunction "4_4") (pintype "passive"))
    )
    (net (code "56") (name "Q5") (class "Default")
      (node (ref "ADDO") (pin "3") (pinfunction "3_3") (pintype "passive"))
      (node (ref "ANDO") (pin "3") (pinfunction "3_3") (pintype "passive"))
      (node (ref "NOTO") (pin "3") (pinfunction "3_3") (pintype "passive"))
      (node (ref "ORO") (pin "3") (pinfunction "3_3") (pintype "passive"))
      (node (ref "OUTI") (pin "3") (pinfunction "3_3") (pintype "passive"))
      (node (ref "R5") (pin "2") (pinfunction "2_2") (pintype "passive"))
      (node (ref "SL") (pin "13") (pinfunction "B6_13") (pintype "bidirectional"))
      (node (ref "SR") (pin "13") (pinfunction "B6_13") (pintype "bidirectional"))
      (node (ref "XORO") (pin "3") (pinfunction "3_3") (pintype "passive"))
    )
    (net (code "57") (name "Q6") (class "Default")
      (node (ref "ADDO") (pin "2") (pinfunction "2_2") (pintype "passive"))
      (node (ref "ANDO") (pin "2") (pinfunction "2_2") (pintype "passive"))
      (node (ref "NOTO") (pin "2") (pinfunction "2_2") (pintype "passive"))
      (node (ref "ORO") (pin "2") (pinfunction "2_2") (pintype "passive"))
      (node (ref "OUTI") (pin "2") (pinfunction "2_2") (pintype "passive"))
      (node (ref "R6") (pin "2") (pinfunction "2_2") (pintype "passive"))
      (node (ref "SL") (pin "12") (pinfunction "B7_12") (pintype "bidirectional"))
      (node (ref "SR") (pin "12") (pinfunction "B7_12") (pintype "bidirectional"))
      (node (ref "XORO") (pin "2") (pinfunction "2_2") (pintype "passive"))
    )
    (net (code "58") (name "Q7") (class "Default")
      (node (ref "ADDO") (pin "1") (pinfunction "1_1") (pintype "passive"))
      (node (ref "ANDO") (pin "1") (pinfunction "1_1") (pintype "passive"))
      (node (ref "NOTO") (pin "1") (pinfunction "1_1") (pintype "passive"))
      (node (ref "ORO") (pin "1") (pinfunction "1_1") (pintype "passive"))
      (node (ref "OUTI") (pin "1") (pinfunction "1_1") (pintype "passive"))
      (node (ref "R7") (pin "2") (pinfunction "2_2") (pintype "passive"))
      (node (ref "SL") (pin "11") (pinfunction "B8_11") (pintype "bidirectional"))
      (node (ref "SR") (pin "11") (pinfunction "B8_11") (pintype "bidirectional"))
      (node (ref "XORO") (pin "1") (pinfunction "1_1") (pintype "passive"))
    )
    (net (code "59") (name "SL-OE") (class "Default")
      (node (ref "CONTROL") (pin "5") (pinfunction "5_5") (pintype "passive"))
      (node (ref "SL") (pin "19") (pinfunction "~{G}_19") (pintype "input"))
    )
    (net (code "60") (name "SR-OE") (class "Default")
      (node (ref "CONTROL") (pin "3") (pinfunction "3_3") (pintype "passive"))
      (node (ref "SR") (pin "19") (pinfunction "~{G}_19") (pintype "input"))
    )
    (net (code "61") (name "SUB") (class "Default")
      (node (ref "CONTROL") (pin "13") (pinfunction "13_13") (pintype "passive"))
      (node (ref "SUB") (pin "1") (pinfunction "1_1") (pintype "passive"))
    )
    (net (code "62") (name "VCC") (class "Default")
      (node (ref "ACCPS") (pin "2") (pinfunction "2_2") (pintype "passive"))
      (node (ref "ADDPS") (pin "2") (pinfunction "2_2") (pintype "passive"))
      (node (ref "ANDPS") (pin "2") (pinfunction "2_2") (pintype "passive"))
      (node (ref "C1") (pin "+") (pinfunction "+_+") (pintype "passive"))
      (node (ref "C10") (pin "+") (pinfunction "+_+") (pintype "passive"))
      (node (ref "C2") (pin "+") (pinfunction "+_+") (pintype "passive"))
      (node (ref "C3") (pin "+") (pinfunction "+_+") (pintype "passive"))
      (node (ref "C4") (pin "+") (pinfunction "+_+") (pintype "passive"))
      (node (ref "C5") (pin "+") (pinfunction "+_+") (pintype "passive"))
      (node (ref "C6") (pin "+") (pinfunction "+_+") (pintype "passive"))
      (node (ref "C7") (pin "+") (pinfunction "+_+") (pintype "passive"))
      (node (ref "C8") (pin "+") (pinfunction "+_+") (pintype "passive"))
      (node (ref "C9") (pin "+") (pinfunction "+_+") (pintype "passive"))
      (node (ref "CMPH") (pin "16") (pinfunction "+UB_16") (pintype "power_in"))
      (node (ref "CMPL") (pin "16") (pinfunction "+UB_16") (pintype "power_in"))
      (node (ref "CMPL") (pin "3") (pinfunction "PEQQ__3") (pintype "input"))
      (node (ref "FLAGS") (pin "1") (pinfunction "~{CLR}_1") (pintype "input"))
      (node (ref "FLAGS") (pin "20") (pinfunction "+UB_20") (pintype "power_in"))
      (node (ref "NOTPS") (pin "2") (pinfunction "2_2") (pintype "passive"))
      (node (ref "ORPS") (pin "2") (pinfunction "2_2") (pintype "passive"))
      (node (ref "OUTPS") (pin "2") (pinfunction "2_2") (pintype "passive"))
      (node (ref "PS") (pin "2") (pinfunction "2_2") (pintype "passive"))
      (node (ref "SL") (pin "1") (pinfunction "DIR_1") (pintype "input"))
      (node (ref "SL") (pin "20") (pinfunction "+UB_20") (pintype "power_in"))
      (node (ref "SR") (pin "1") (pinfunction "DIR_1") (pintype "input"))
      (node (ref "SR") (pin "20") (pinfunction "+UB_20") (pintype "power_in"))
      (node (ref "XORPS") (pin "2") (pinfunction "2_2") (pintype "passive"))
    )
    (net (code "63") (name "XOR-OE") (class "Default")
      (node (ref "CONTROL") (pin "7") (pinfunction "7_7") (pintype "passive"))
      (node (ref "XORCT") (pin "1") (pinfunction "1_1") (pintype "passive"))
    )
    (net (code "64") (name "ZERO") (class "Default")
      (node (ref "FLAG") (pin "1") (pinfunction "1_1") (pintype "passive"))
      (node (ref "FLAGS") (pin "2") (pinfunction "1Q_2") (pintype "output"))
    )
    (net (code "65") (name "ZF") (class "Default")
      (node (ref "FLAGS") (pin "3") (pinfunction "1D_3") (pintype "input"))
      (node (ref "LZF") (pin "A") (pinfunction "A_A") (pintype "passive"))
      (node (ref "ZF") (pin "1") (pinfunction "1_1") (pintype "passive"))
    )
    (net (code "66") (name "unconnected-(CONTROL-Pad14)") (class "Default")
      (node (ref "CONTROL") (pin "14") (pinfunction "14_14") (pintype "passive"))
    )
    (net (code "67") (name "unconnected-(FLAGSC-7D-Pad17)") (class "Default")
      (node (ref "FLAGS") (pin "17") (pinfunction "7D_17") (pintype "input"))
    )
    (net (code "68") (name "unconnected-(FLAGSC-7Q-Pad16)") (class "Default")
      (node (ref "FLAGS") (pin "16") (pinfunction "7Q_16") (pintype "output"))
    )
    (net (code "69") (name "unconnected-(FLAGSC-8D-Pad18)") (class "Default")
      (node (ref "FLAGS") (pin "18") (pinfunction "8D_18") (pintype "input"))
    )
    (net (code "70") (name "unconnected-(FLAGSC-8Q-Pad19)") (class "Default")
      (node (ref "FLAGS") (pin "19") (pinfunction "8Q_19") (pintype "output"))
    )
  )
)
